# Sheet1.net
KiCad netlist of a schematic drawn in Altium Designer
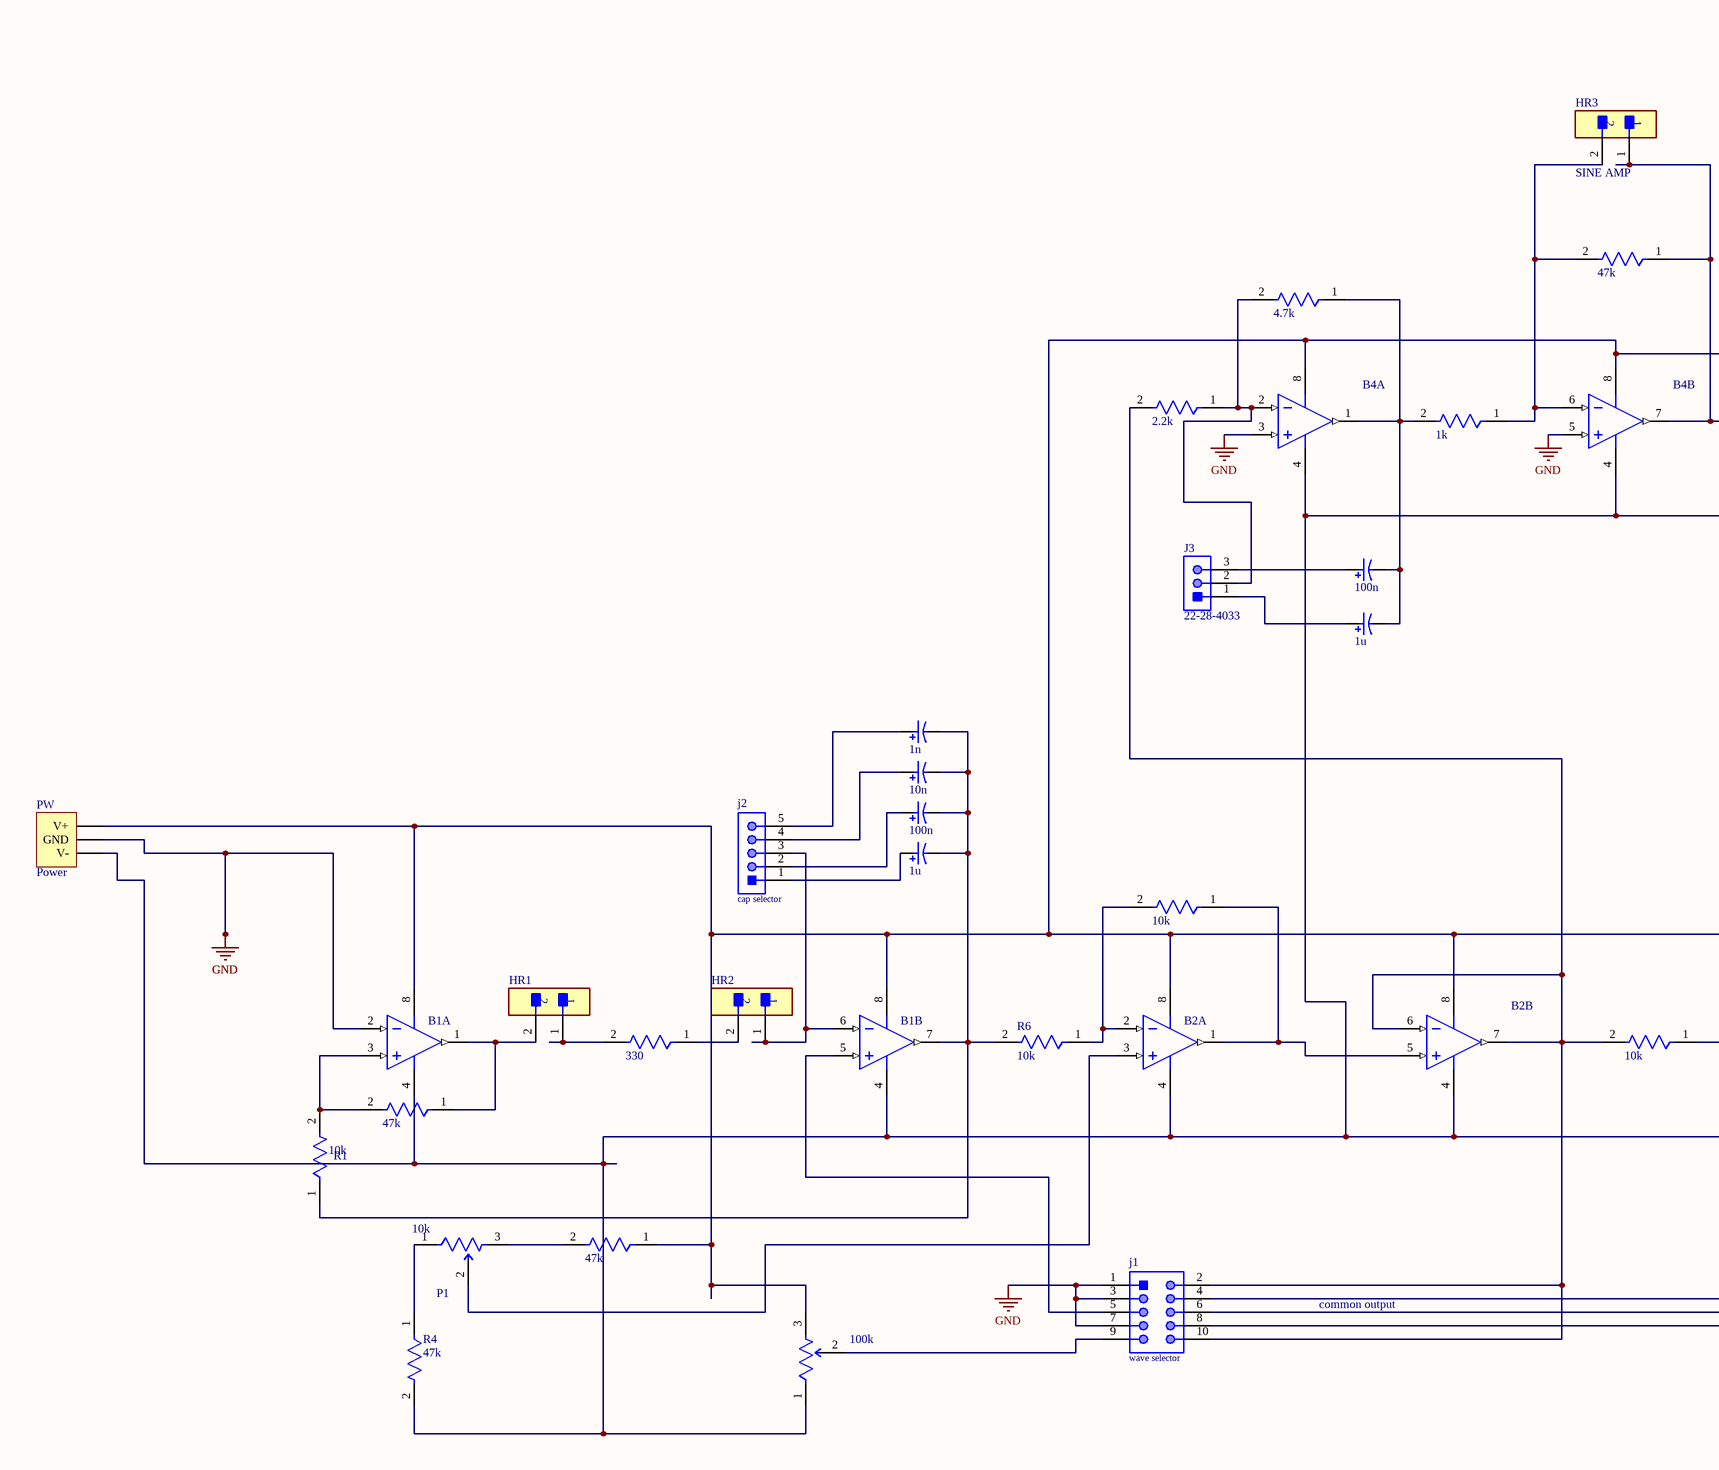
[diagram p0: Sheet1.SchDoc, left]
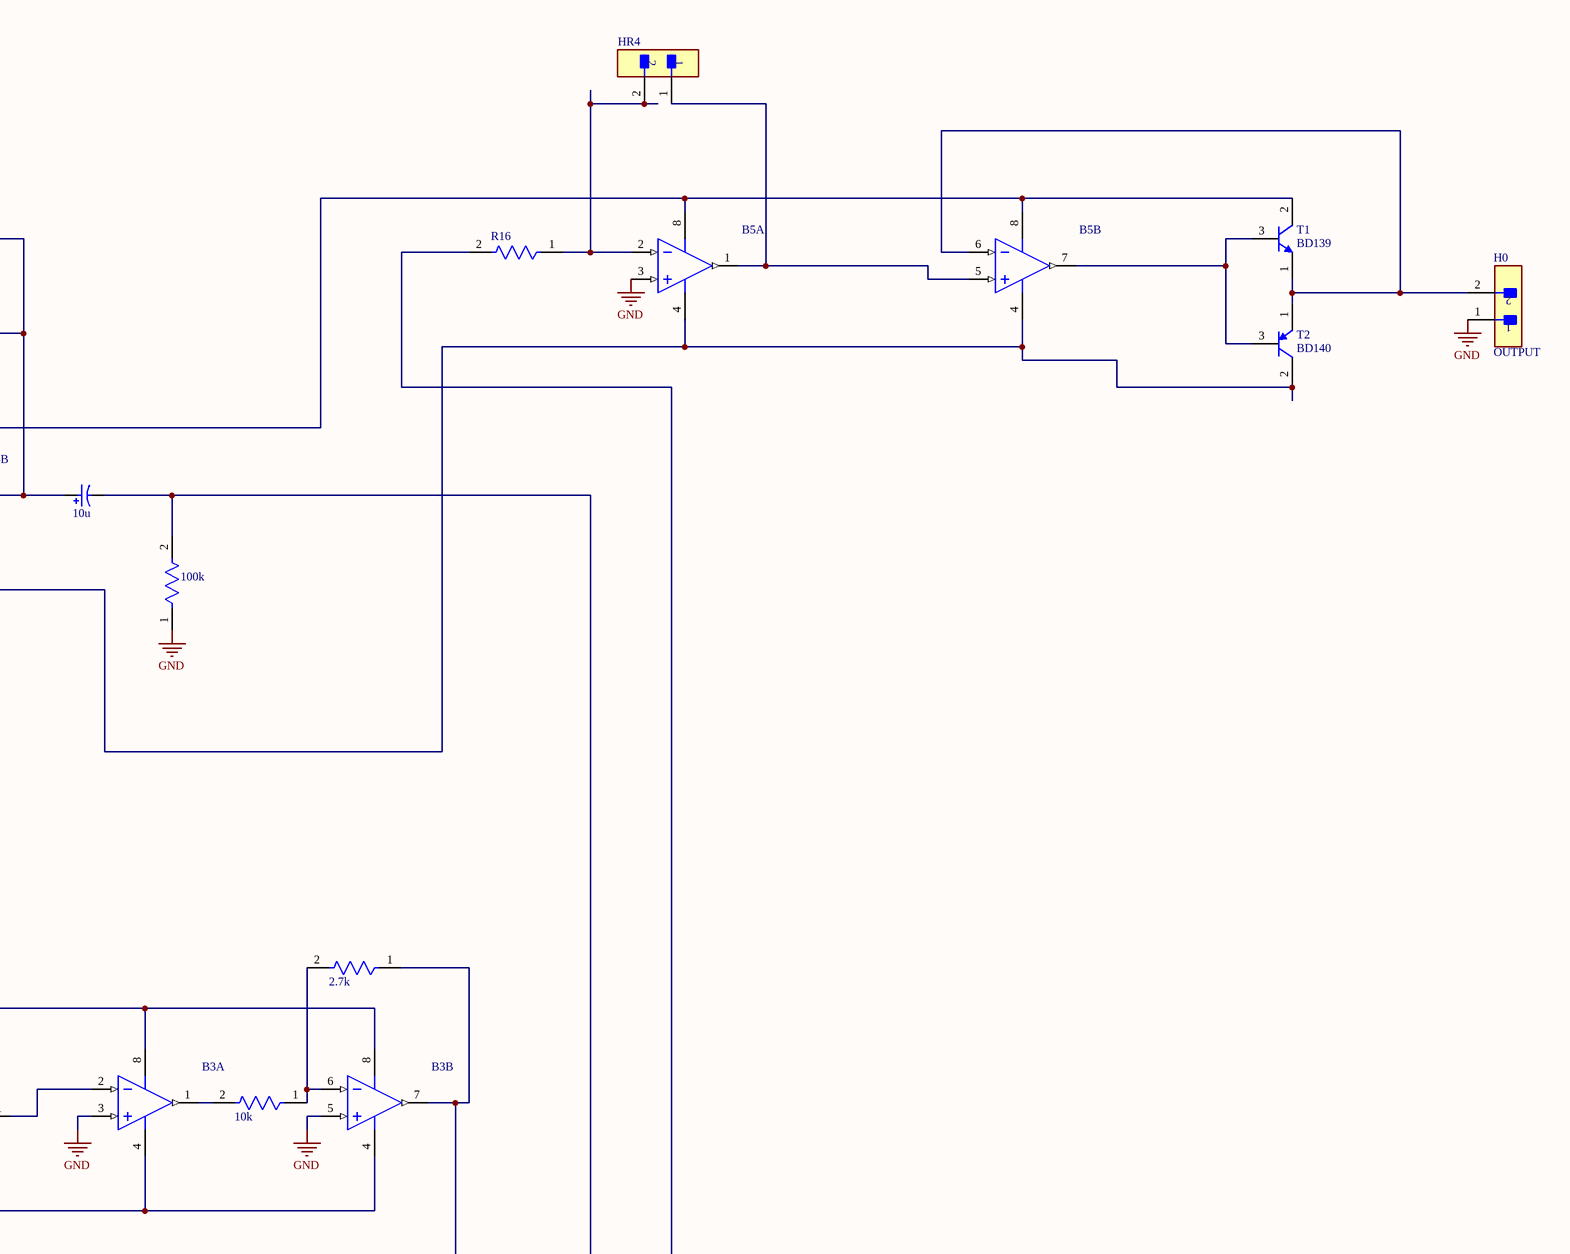
[diagram p1: Sheet1.SchDoc, right]

(export (version "E")
  (design (tool "Eeschema 10.0.6"))
  (components
    (comp (ref "B1")
      (value "integrator")
      (footprint "ADI-N-8")
      (fields
        (field (name "MANUFACTURER") "Analog Devices")
        (field (name "PARTNUMBER") "AD826ANZ")
        (field (name "GENERIC PART NUMBER") "AD826")
      )
      (libsource (lib "Altium Content Vault") (part "ADI-AD7xx_8xx-X-8"))
    )
    (comp (ref "B2")
      (value "comparator gain")
      (footprint "ADI-N-8")
      (fields
        (field (name "MANUFACTURER") "Analog Devices")
        (field (name "PARTNUMBER") "AD826ANZ")
        (field (name "GENERIC PART NUMBER") "AD826")
      )
      (libsource (lib "Altium Content Vault") (part "ADI-AD7xx_8xx-X-8"))
    )
    (comp (ref "B3")
      (value "AD826ANZ")
      (footprint "ADI-N-8")
      (fields (field (name "MANUFACTURER") "Analog Devices") (field (name "GENERIC PART NUMBER") "AD826"))
      (libsource (lib "Altium Content Vault") (part "ADI-AD7xx_8xx-X-8"))
    )
    (comp (ref "B4")
      (value "AD826ANZ")
      (footprint "ADI-N-8")
      (fields (field (name "MANUFACTURER") "Analog Devices") (field (name "GENERIC PART NUMBER") "AD826"))
      (libsource (lib "Altium Content Vault") (part "ADI-AD7xx_8xx-X-8"))
    )
    (comp (ref "B5")
      (value "AD826ANZ")
      (footprint "ADI-N-8")
      (fields (field (name "MANUFACTURER") "Analog Devices") (field (name "GENERIC PART NUMBER") "AD826"))
      (libsource (lib "Altium Content Vault") (part "ADI-AD7xx_8xx-X-8"))
    )
    (comp (ref "C1")
      (value "1n")
      (footprint "CAPPR55-250-1120X630X1220")
      (fields (field (name "MANUFACTURER") "Panasonic"))
      (libsource (lib "Altium Content Vault") (part "CAP-P-2"))
    )
    (comp (ref "C2")
      (value "10n")
      (footprint "CAPPR55-250-1120X630X1220")
      (fields (field (name "MANUFACTURER") "Panasonic"))
      (libsource (lib "Altium Content Vault") (part "CAP-P-2"))
    )
    (comp (ref "C3")
      (value "100n")
      (footprint "CAPPR55-250-1120X630X1220")
      (fields (field (name "MANUFACTURER") "Panasonic"))
      (libsource (lib "Altium Content Vault") (part "CAP-P-2"))
    )
    (comp (ref "C4")
      (value "1u")
      (footprint "CAPPR55-250-1120X630X1220")
      (fields (field (name "MANUFACTURER") "Panasonic"))
      (libsource (lib "Altium Content Vault") (part "CAP-P-2"))
    )
    (comp (ref "C5")
      (value "100n")
      (footprint "CAPPR55-250-1120X630X1220")
      (fields (field (name "MANUFACTURER") "Panasonic"))
      (libsource (lib "Altium Content Vault") (part "CAP-P-2"))
    )
    (comp (ref "C6")
      (value "1u")
      (footprint "CAPPR55-250-1120X630X1220")
      (fields (field (name "MANUFACTURER") "Panasonic"))
      (libsource (lib "Altium Content Vault") (part "CAP-P-2"))
    )
    (comp (ref "C7")
      (value "10u")
      (footprint "CAPPR55-250-1120X630X1220")
      (fields (field (name "MANUFACTURER") "Panasonic"))
      (libsource (lib "Altium Content Vault") (part "CAP-P-2"))
    )
    (comp (ref "H0")
      (value "OUTPUT")
      (footprint "FP-TSW-102-07-L-S-MFG")
      (description "CONN HEADER VERT 2POS 2.54MM")
      (libsource (lib "") (part "3bc925449376181038e59eaffc5286c_1"))
    )
    (comp (ref "HR1")
      (value "FREQ")
      (footprint "FP-TSW-102-07-L-S-MFG")
      (description "CONN HEADER VERT 2POS 2.54MM")
      (libsource (lib "Altium Content Vault") (part "3bc925449376181038e59eaffc5286c"))
    )
    (comp (ref "HR2")
      (value "FREQ")
      (footprint "FP-TSW-102-07-L-S-MFG")
      (description "CONN HEADER VERT 2POS 2.54MM")
      (libsource (lib "Altium Content Vault") (part "3bc925449376181038e59eaffc5286c"))
    )
    (comp (ref "HR3")
      (value "SINE AMP")
      (footprint "FP-TSW-102-07-L-S-MFG")
      (description "CONN HEADER VERT 2POS 2.54MM")
      (libsource (lib "Altium Content Vault") (part "3bc925449376181038e59eaffc5286c"))
    )
    (comp (ref "HR4")
      (value "AMP")
      (footprint "FP-TSW-102-07-L-S-MFG")
      (description "CONN HEADER VERT 2POS 2.54MM")
      (libsource (lib "Altium Content Vault") (part "3bc925449376181038e59eaffc5286c"))
    )
    (comp (ref "j1")
      (value "wave selector")
      (footprint "61301021121")
      (description "THT Vertical Pin Header WR-PHD, Pitch 2.54 mm, Dual Row, 10 pins")
      (fields
        (field (name "MANUFACTURER") "Wurth Elektronik")
        (field (name "PART NUMBER") "61301021121")
        (field (name "PUBLISHER") "WurthElektronik")
      )
      (libsource (lib "Altium Content Vault") (part "WE-CN-2P-M-R10"))
    )
    (comp (ref "j2")
      (value "cap selector")
      (footprint "61300511121")
      (description "THT Vertical Pin Header WR-PHD, Pitch 2.54 mm, Single Row, 5 pins")
      (fields
        (field (name "PART NUMBER") "61300511121")
        (field (name "MANUFACTURER") "Wurth Elektronik")
        (field (name "PUBLISHER") "WurthElektronik")
      )
      (libsource (lib "Altium Content Vault") (part "WE-CN-1P-M-R5"))
    )
    (comp (ref "J3")
      (value "22-28-4033")
      (footprint "MOLX-22-28-4033_V")
      (description "Male Header, Pitch 2.54 mm, 1 x 3 Position, Height 8.38 mm, Tail Length 3.18 mm, RoHS, Bulk")
      (fields (field (name "MANUFACTURER") "Molex"))
      (libsource (lib "Altium Content Vault") (part "CN-1P-M-R3"))
    )
    (comp (ref "P1")
      (value "10k")
      (footprint "FP-3362P-1-503TLF-MFG")
      (description "TRIMMER 50K OHM 0.5W PC PIN TOP")
      (fields (field (name "TOLERANCE") "10%"))
      (libsource (lib "Altium Content Vault") (part "2dcfd2547301a7d3209a5e99acfd772"))
    )
    (comp (ref "P2")
      (value "100k")
      (footprint "FP-3362P-1-503TLF-MFG")
      (description "TRIMMER 50K OHM 0.5W PC PIN TOP")
      (fields (field (name "TOLERANCE") "10%"))
      (libsource (lib "Altium Content Vault") (part "2dcfd2547301a7d3209a5e99acfd772"))
    )
    (comp (ref "PW")
      (value "Power")
      (footprint "HDR1X3")
      (description "Header, 3-Pin")
      (fields (field (name "PUBLISHER") "Altium Limited"))
      (libsource (lib "Miscellaneous Connectors") (part "Header 3"))
    )
    (comp (ref "R1")
      (value "10k")
      (footprint "FP-CF18-MFG")
      (description "RES 10K OHM 1/8W 5% CF AXIAL")
      (fields
        (field (name "MANUFACTURER PART NUMBER") "CF18JT10K0")
        (field (name "MANUFACTURER") "Stackpole Electronics")
      )
      (libsource (lib "Altium Content Vault") (part "1029c3af85768c4190bb7ad29bc67b5"))
    )
    (comp (ref "R2")
      (value "47k")
      (footprint "FP-CF18-MFG")
      (description "RES 10K OHM 1/8W 5% CF AXIAL")
      (fields
        (field (name "MANUFACTURER PART NUMBER") "CF18JT10K0")
        (field (name "MANUFACTURER") "Stackpole Electronics")
      )
      (libsource (lib "Altium Content Vault") (part "1029c3af85768c4190bb7ad29bc67b5"))
    )
    (comp (ref "R3")
      (value "330")
      (footprint "FP-CF18-MFG")
      (description "RES 10K OHM 1/8W 5% CF AXIAL")
      (fields
        (field (name "MANUFACTURER PART NUMBER") "CF18JT10K0")
        (field (name "MANUFACTURER") "Stackpole Electronics")
      )
      (libsource (lib "Altium Content Vault") (part "1029c3af85768c4190bb7ad29bc67b5"))
    )
    (comp (ref "R4")
      (value "47k")
      (footprint "FP-CF18-MFG")
      (description "RES 10K OHM 1/8W 5% CF AXIAL")
      (fields
        (field (name "MANUFACTURER PART NUMBER") "CF18JT10K0")
        (field (name "MANUFACTURER") "Stackpole Electronics")
      )
      (libsource (lib "Altium Content Vault") (part "1029c3af85768c4190bb7ad29bc67b5"))
    )
    (comp (ref "R5")
      (value "47k")
      (footprint "FP-CF18-MFG")
      (description "RES 10K OHM 1/8W 5% CF AXIAL")
      (fields
        (field (name "MANUFACTURER PART NUMBER") "CF18JT10K0")
        (field (name "MANUFACTURER") "Stackpole Electronics")
      )
      (libsource (lib "Altium Content Vault") (part "1029c3af85768c4190bb7ad29bc67b5"))
    )
    (comp (ref "R6")
      (value "10k")
      (footprint "FP-CF18-MFG")
      (description "RES 10K OHM 1/8W 5% CF AXIAL")
      (fields
        (field (name "MANUFACTURER PART NUMBER") "CF18JT10K0")
        (field (name "MANUFACTURER") "Stackpole Electronics")
      )
      (libsource (lib "Altium Content Vault") (part "1029c3af85768c4190bb7ad29bc67b5"))
    )
    (comp (ref "R7")
      (value "10k")
      (footprint "FP-CF18-MFG")
      (description "RES 10K OHM 1/8W 5% CF AXIAL")
      (fields
        (field (name "MANUFACTURER PART NUMBER") "CF18JT10K0")
        (field (name "MANUFACTURER") "Stackpole Electronics")
      )
      (libsource (lib "Altium Content Vault") (part "1029c3af85768c4190bb7ad29bc67b5"))
    )
    (comp (ref "R8")
      (value "10k")
      (footprint "FP-CF18-MFG")
      (description "RES 10K OHM 1/8W 5% CF AXIAL")
      (fields
        (field (name "MANUFACTURER PART NUMBER") "CF18JT10K0")
        (field (name "MANUFACTURER") "Stackpole Electronics")
      )
      (libsource (lib "Altium Content Vault") (part "1029c3af85768c4190bb7ad29bc67b5"))
    )
    (comp (ref "R9")
      (value "10k")
      (footprint "FP-CF18-MFG")
      (description "RES 10K OHM 1/8W 5% CF AXIAL")
      (fields
        (field (name "MANUFACTURER PART NUMBER") "CF18JT10K0")
        (field (name "MANUFACTURER") "Stackpole Electronics")
      )
      (libsource (lib "Altium Content Vault") (part "1029c3af85768c4190bb7ad29bc67b5"))
    )
    (comp (ref "R10")
      (value "2.7k")
      (footprint "FP-CF18-MFG")
      (description "RES 10K OHM 1/8W 5% CF AXIAL")
      (fields
        (field (name "MANUFACTURER PART NUMBER") "CF18JT10K0")
        (field (name "MANUFACTURER") "Stackpole Electronics")
      )
      (libsource (lib "Altium Content Vault") (part "1029c3af85768c4190bb7ad29bc67b5"))
    )
    (comp (ref "R11")
      (value "2.2k")
      (footprint "FP-CF18-MFG")
      (description "RES 10K OHM 1/8W 5% CF AXIAL")
      (fields
        (field (name "MANUFACTURER PART NUMBER") "CF18JT10K0")
        (field (name "MANUFACTURER") "Stackpole Electronics")
      )
      (libsource (lib "Altium Content Vault") (part "1029c3af85768c4190bb7ad29bc67b5"))
    )
    (comp (ref "R12")
      (value "4.7k")
      (footprint "FP-CF18-MFG")
      (description "RES 10K OHM 1/8W 5% CF AXIAL")
      (fields
        (field (name "MANUFACTURER PART NUMBER") "CF18JT10K0")
        (field (name "MANUFACTURER") "Stackpole Electronics")
      )
      (libsource (lib "Altium Content Vault") (part "1029c3af85768c4190bb7ad29bc67b5"))
    )
    (comp (ref "R13")
      (value "1k")
      (footprint "FP-CF18-MFG")
      (description "RES 10K OHM 1/8W 5% CF AXIAL")
      (fields
        (field (name "MANUFACTURER PART NUMBER") "CF18JT10K0")
        (field (name "MANUFACTURER") "Stackpole Electronics")
      )
      (libsource (lib "Altium Content Vault") (part "1029c3af85768c4190bb7ad29bc67b5"))
    )
    (comp (ref "R14")
      (value "47k")
      (footprint "FP-CF18-MFG")
      (description "RES 10K OHM 1/8W 5% CF AXIAL")
      (fields
        (field (name "MANUFACTURER PART NUMBER") "CF18JT10K0")
        (field (name "MANUFACTURER") "Stackpole Electronics")
      )
      (libsource (lib "Altium Content Vault") (part "1029c3af85768c4190bb7ad29bc67b5"))
    )
    (comp (ref "R15")
      (value "100k")
      (footprint "FP-CF18-MFG")
      (description "RES 10K OHM 1/8W 5% CF AXIAL")
      (fields
        (field (name "MANUFACTURER PART NUMBER") "CF18JT10K0")
        (field (name "MANUFACTURER") "Stackpole Electronics")
      )
      (libsource (lib "Altium Content Vault") (part "1029c3af85768c4190bb7ad29bc67b5"))
    )
    (comp (ref "R16")
      (value "10k")
      (footprint "FP-CF18-MFG")
      (description "RES 10K OHM 1/8W 5% CF AXIAL")
      (fields
        (field (name "MANUFACTURER PART NUMBER") "CF18JT10K0")
        (field (name "MANUFACTURER") "Stackpole Electronics")
      )
      (libsource (lib "Altium Content Vault") (part "1029c3af85768c4190bb7ad29bc67b5"))
    )
    (comp (ref "T1")
      (value "BD139")
      (footprint "ONSC-TO-225-3-77-09")
      (description "Plastic Medium-Power Silicon NPN Transistor, 3-Pin TO-225, Bulk Box")
      (fields (field (name "MANUFACTURER") "On Semiconductor"))
      (libsource (lib "Altium Content Vault") (part "ONSC-NPN-E1C2B3-3"))
    )
    (comp (ref "T2")
      (value "BD140")
      (footprint "ONSC-TO-225-3-77-09")
      (description "Plastic Medium-Power Silicon PNP Transistor, 3-Pin TO-225, Bulk Box")
      (fields (field (name "MANUFACTURER") "On Semiconductor"))
      (libsource (lib "Altium Content Vault") (part "ONSC-PNP-E1C2B3-3"))
    )
  )
  (nets
    (net (code "1") (name "GND") (class "Default")
      (node (ref "B1") (pin "2") (pinfunction "-IN_1_2") (pintype "input"))
      (node (ref "B3") (pin "3") (pinfunction "+IN_1_3") (pintype "input"))
      (node (ref "B3") (pin "5") (pinfunction "+IN_2_5") (pintype "input"))
      (node (ref "B4") (pin "3") (pinfunction "+IN_1_3") (pintype "input"))
      (node (ref "B4") (pin "5") (pinfunction "+IN_2_5") (pintype "input"))
      (node (ref "B5") (pin "3") (pinfunction "+IN_1_3") (pintype "input"))
      (node (ref "H0") (pin "1") (pinfunction "1_1") (pintype "passive"))
      (node (ref "PW") (pin "2") (pinfunction "GND_2") (pintype "passive"))
      (node (ref "R15") (pin "1") (pinfunction "1_1") (pintype "passive"))
      (node (ref "j1") (pin "1") (pinfunction "1_1") (pintype "passive"))
      (node (ref "j1") (pin "3") (pinfunction "3_3") (pintype "passive"))
      (node (ref "j1") (pin "7") (pinfunction "7_7") (pintype "passive"))
    )
    (net (code "2") (name "Net-(B1A-+IN_1)") (class "Default")
      (node (ref "B1") (pin "3") (pinfunction "+IN_1_3") (pintype "input"))
      (node (ref "R1") (pin "2") (pinfunction "2_2") (pintype "passive"))
      (node (ref "R2") (pin "2") (pinfunction "2_2") (pintype "passive"))
    )
    (net (code "3") (name "Net-(B1A-+V)") (class "Default")
      (node (ref "B1") (pin "8") (pinfunction "+V_8") (pintype "power_in"))
      (node (ref "B2") (pin "8") (pinfunction "+V_8") (pintype "power_in"))
      (node (ref "B3") (pin "8") (pinfunction "+V_8") (pintype "power_in"))
      (node (ref "B4") (pin "8") (pinfunction "+V_8") (pintype "power_in"))
      (node (ref "B5") (pin "8") (pinfunction "+V_8") (pintype "power_in"))
      (node (ref "P2") (pin "3") (pinfunction "CW_3") (pintype "passive"))
      (node (ref "PW") (pin "1") (pinfunction "V+_1") (pintype "passive"))
      (node (ref "R5") (pin "1") (pinfunction "1_1") (pintype "passive"))
      (node (ref "T1") (pin "2") (pinfunction "C_2") (pintype "passive"))
    )
    (net (code "4") (name "Net-(B1A--V)") (class "Default")
      (node (ref "B1") (pin "4") (pinfunction "-V_4") (pintype "power_in"))
      (node (ref "B2") (pin "4") (pinfunction "-V_4") (pintype "power_in"))
      (node (ref "B3") (pin "4") (pinfunction "-V_4") (pintype "power_in"))
      (node (ref "B4") (pin "4") (pinfunction "-V_4") (pintype "power_in"))
      (node (ref "B5") (pin "4") (pinfunction "-V_4") (pintype "power_in"))
      (node (ref "P2") (pin "1") (pinfunction "CCW_1") (pintype "passive"))
      (node (ref "PW") (pin "3") (pinfunction "V-_3") (pintype "passive"))
      (node (ref "R4") (pin "2") (pinfunction "2_2") (pintype "passive"))
      (node (ref "T2") (pin "2") (pinfunction "C_2") (pintype "passive"))
    )
    (net (code "5") (name "Net-(B1A-OUT_1)") (class "Default")
      (node (ref "B1") (pin "1") (pinfunction "OUT_1_1") (pintype "output"))
      (node (ref "HR1") (pin "2") (pinfunction "2_2") (pintype "passive"))
      (node (ref "R2") (pin "1") (pinfunction "1_1") (pintype "passive"))
    )
    (net (code "6") (name "Net-(B1B-+IN_2)") (class "Default")
      (node (ref "B1") (pin "5") (pinfunction "+IN_2_5") (pintype "input"))
      (node (ref "j1") (pin "5") (pinfunction "5_5") (pintype "passive"))
    )
    (net (code "7") (name "Net-(B1B--IN_2)") (class "Default")
      (node (ref "B1") (pin "6") (pinfunction "-IN_2_6") (pintype "input"))
      (node (ref "HR2") (pin "1") (pinfunction "1_1") (pintype "passive"))
      (node (ref "j2") (pin "3") (pinfunction "3_3") (pintype "passive"))
    )
    (net (code "8") (name "Net-(B1B-OUT_2)") (class "Default")
      (node (ref "B1") (pin "7") (pinfunction "OUT_2_7") (pintype "output"))
      (node (ref "C1") (pin "2") (pinfunction "2_2") (pintype "passive"))
      (node (ref "C2") (pin "2") (pinfunction "2_2") (pintype "passive"))
      (node (ref "C3") (pin "2") (pinfunction "2_2") (pintype "passive"))
      (node (ref "C4") (pin "2") (pinfunction "2_2") (pintype "passive"))
      (node (ref "R1") (pin "1") (pinfunction "1_1") (pintype "passive"))
      (node (ref "R6") (pin "2") (pinfunction "2_2") (pintype "passive"))
    )
    (net (code "9") (name "Net-(B2A-+IN_1)") (class "Default")
      (node (ref "B2") (pin "3") (pinfunction "+IN_1_3") (pintype "input"))
      (node (ref "P1") (pin "2") (pinfunction "WIPER_2") (pintype "passive"))
    )
    (net (code "10") (name "Net-(B2A--IN_1)") (class "Default")
      (node (ref "B2") (pin "2") (pinfunction "-IN_1_2") (pintype "input"))
      (node (ref "R6") (pin "1") (pinfunction "1_1") (pintype "passive"))
      (node (ref "R7") (pin "2") (pinfunction "2_2") (pintype "passive"))
    )
    (net (code "11") (name "Net-(B2A-OUT_1)") (class "Default")
      (node (ref "B2") (pin "1") (pinfunction "OUT_1_1") (pintype "output"))
      (node (ref "B2") (pin "5") (pinfunction "+IN_2_5") (pintype "input"))
      (node (ref "R7") (pin "1") (pinfunction "1_1") (pintype "passive"))
    )
    (net (code "12") (name "Net-(B2B--IN_2)") (class "Default")
      (node (ref "B2") (pin "6") (pinfunction "-IN_2_6") (pintype "input"))
      (node (ref "B2") (pin "7") (pinfunction "OUT_2_7") (pintype "output"))
      (node (ref "R11") (pin "2") (pinfunction "2_2") (pintype "passive"))
      (node (ref "R8") (pin "2") (pinfunction "2_2") (pintype "passive"))
      (node (ref "j1") (pin "10") (pinfunction "10_10") (pintype "passive"))
      (node (ref "j1") (pin "2") (pinfunction "2_2") (pintype "passive"))
    )
    (net (code "13") (name "Net-(B3A--IN_1)") (class "Default")
      (node (ref "B3") (pin "2") (pinfunction "-IN_1_2") (pintype "input"))
      (node (ref "R8") (pin "1") (pinfunction "1_1") (pintype "passive"))
    )
    (net (code "14") (name "Net-(B3A-OUT_1)") (class "Default")
      (node (ref "B3") (pin "1") (pinfunction "OUT_1_1") (pintype "output"))
      (node (ref "R9") (pin "2") (pinfunction "2_2") (pintype "passive"))
    )
    (net (code "15") (name "Net-(B3B--IN_2)") (class "Default")
      (node (ref "B3") (pin "6") (pinfunction "-IN_2_6") (pintype "input"))
      (node (ref "R10") (pin "2") (pinfunction "2_2") (pintype "passive"))
      (node (ref "R9") (pin "1") (pinfunction "1_1") (pintype "passive"))
    )
    (net (code "16") (name "Net-(B3B-OUT_2)") (class "Default")
      (node (ref "B3") (pin "7") (pinfunction "OUT_2_7") (pintype "output"))
      (node (ref "R10") (pin "1") (pinfunction "1_1") (pintype "passive"))
      (node (ref "j1") (pin "4") (pinfunction "4_4") (pintype "passive"))
    )
    (net (code "17") (name "Net-(B4A--IN_1)") (class "Default")
      (node (ref "B4") (pin "2") (pinfunction "-IN_1_2") (pintype "input"))
      (node (ref "J3") (pin "2") (pinfunction "2_2") (pintype "passive"))
      (node (ref "R11") (pin "1") (pinfunction "1_1") (pintype "passive"))
      (node (ref "R12") (pin "2") (pinfunction "2_2") (pintype "passive"))
    )
    (net (code "18") (name "Net-(B4A-OUT_1)") (class "Default")
      (node (ref "B4") (pin "1") (pinfunction "OUT_1_1") (pintype "output"))
      (node (ref "C5") (pin "2") (pinfunction "2_2") (pintype "passive"))
      (node (ref "C6") (pin "2") (pinfunction "2_2") (pintype "passive"))
      (node (ref "R12") (pin "1") (pinfunction "1_1") (pintype "passive"))
      (node (ref "R13") (pin "2") (pinfunction "2_2") (pintype "passive"))
    )
    (net (code "19") (name "Net-(B4B--IN_2)") (class "Default")
      (node (ref "B4") (pin "6") (pinfunction "-IN_2_6") (pintype "input"))
      (node (ref "HR3") (pin "2") (pinfunction "2_2") (pintype "passive"))
      (node (ref "R13") (pin "1") (pinfunction "1_1") (pintype "passive"))
      (node (ref "R14") (pin "2") (pinfunction "2_2") (pintype "passive"))
    )
    (net (code "20") (name "Net-(B4B-OUT_2)") (class "Default")
      (node (ref "B4") (pin "7") (pinfunction "OUT_2_7") (pintype "output"))
      (node (ref "C7") (pin "1") (pinfunction "1_1") (pintype "passive"))
      (node (ref "HR3") (pin "1") (pinfunction "1_1") (pintype "passive"))
      (node (ref "R14") (pin "1") (pinfunction "1_1") (pintype "passive"))
    )
    (net (code "21") (name "Net-(B5A--IN_1)") (class "Default")
      (node (ref "B5") (pin "2") (pinfunction "-IN_1_2") (pintype "input"))
      (node (ref "HR4") (pin "2") (pinfunction "2_2") (pintype "passive"))
      (node (ref "R16") (pin "1") (pinfunction "1_1") (pintype "passive"))
    )
    (net (code "22") (name "Net-(B5A-OUT_1)") (class "Default")
      (node (ref "B5") (pin "1") (pinfunction "OUT_1_1") (pintype "output"))
      (node (ref "B5") (pin "5") (pinfunction "+IN_2_5") (pintype "input"))
      (node (ref "HR4") (pin "1") (pinfunction "1_1") (pintype "passive"))
    )
    (net (code "23") (name "Net-(B5B--IN_2)") (class "Default")
      (node (ref "B5") (pin "6") (pinfunction "-IN_2_6") (pintype "input"))
      (node (ref "H0") (pin "2") (pinfunction "2_2") (pintype "passive"))
      (node (ref "T1") (pin "1") (pinfunction "E_1") (pintype "passive"))
      (node (ref "T2") (pin "1") (pinfunction "E_1") (pintype "passive"))
    )
    (net (code "24") (name "Net-(B5B-OUT_2)") (class "Default")
      (node (ref "B5") (pin "7") (pinfunction "OUT_2_7") (pintype "output"))
      (node (ref "T1") (pin "3") (pinfunction "B_3") (pintype "passive"))
      (node (ref "T2") (pin "3") (pinfunction "B_3") (pintype "passive"))
    )
    (net (code "25") (name "Net-(C1-Pad1)") (class "Default")
      (node (ref "C1") (pin "1") (pinfunction "1_1") (pintype "passive"))
      (node (ref "j2") (pin "5") (pinfunction "5_5") (pintype "passive"))
    )
    (net (code "26") (name "Net-(C2-Pad1)") (class "Default")
      (node (ref "C2") (pin "1") (pinfunction "1_1") (pintype "passive"))
      (node (ref "j2") (pin "4") (pinfunction "4_4") (pintype "passive"))
    )
    (net (code "27") (name "Net-(C3-Pad1)") (class "Default")
      (node (ref "C3") (pin "1") (pinfunction "1_1") (pintype "passive"))
      (node (ref "j2") (pin "2") (pinfunction "2_2") (pintype "passive"))
    )
    (net (code "28") (name "Net-(C4-Pad1)") (class "Default")
      (node (ref "C4") (pin "1") (pinfunction "1_1") (pintype "passive"))
      (node (ref "j2") (pin "1") (pinfunction "1_1") (pintype "passive"))
    )
    (net (code "29") (name "Net-(C5-Pad1)") (class "Default")
      (node (ref "C5") (pin "1") (pinfunction "1_1") (pintype "passive"))
      (node (ref "J3") (pin "3") (pinfunction "3_3") (pintype "passive"))
    )
    (net (code "30") (name "Net-(C6-Pad1)") (class "Default")
      (node (ref "C6") (pin "1") (pinfunction "1_1") (pintype "passive"))
      (node (ref "J3") (pin "1") (pinfunction "1_1") (pintype "passive"))
    )
    (net (code "31") (name "Net-(C7-Pad2)") (class "Default")
      (node (ref "C7") (pin "2") (pinfunction "2_2") (pintype "passive"))
      (node (ref "R15") (pin "2") (pinfunction "2_2") (pintype "passive"))
      (node (ref "j1") (pin "8") (pinfunction "8_8") (pintype "passive"))
    )
    (net (code "32") (name "Net-(HR1-Pad1)") (class "Default")
      (node (ref "HR1") (pin "1") (pinfunction "1_1") (pintype "passive"))
      (node (ref "R3") (pin "2") (pinfunction "2_2") (pintype "passive"))
    )
    (net (code "33") (name "Net-(HR2-Pad2)") (class "Default")
      (node (ref "HR2") (pin "2") (pinfunction "2_2") (pintype "passive"))
      (node (ref "R3") (pin "1") (pinfunction "1_1") (pintype "passive"))
    )
    (net (code "34") (name "Net-(P1-CCW)") (class "Default")
      (node (ref "P1") (pin "1") (pinfunction "CCW_1") (pintype "passive"))
      (node (ref "R4") (pin "1") (pinfunction "1_1") (pintype "passive"))
    )
    (net (code "35") (name "Net-(P1-CW)") (class "Default")
      (node (ref "P1") (pin "3") (pinfunction "CW_3") (pintype "passive"))
      (node (ref "R5") (pin "2") (pinfunction "2_2") (pintype "passive"))
    )
    (net (code "36") (name "Net-(P2-WIPER)") (class "Default")
      (node (ref "P2") (pin "2") (pinfunction "WIPER_2") (pintype "passive"))
      (node (ref "j1") (pin "9") (pinfunction "9_9") (pintype "passive"))
    )
    (net (code "37") (name "Net-(R16-Pad2)") (class "Default")
      (node (ref "R16") (pin "2") (pinfunction "2_2") (pintype "passive"))
      (node (ref "j1") (pin "6") (pinfunction "6_6") (pintype "passive"))
    )
  )
)
